# powersense.net
KiCad netlist of a schematic drawn in EAGLE
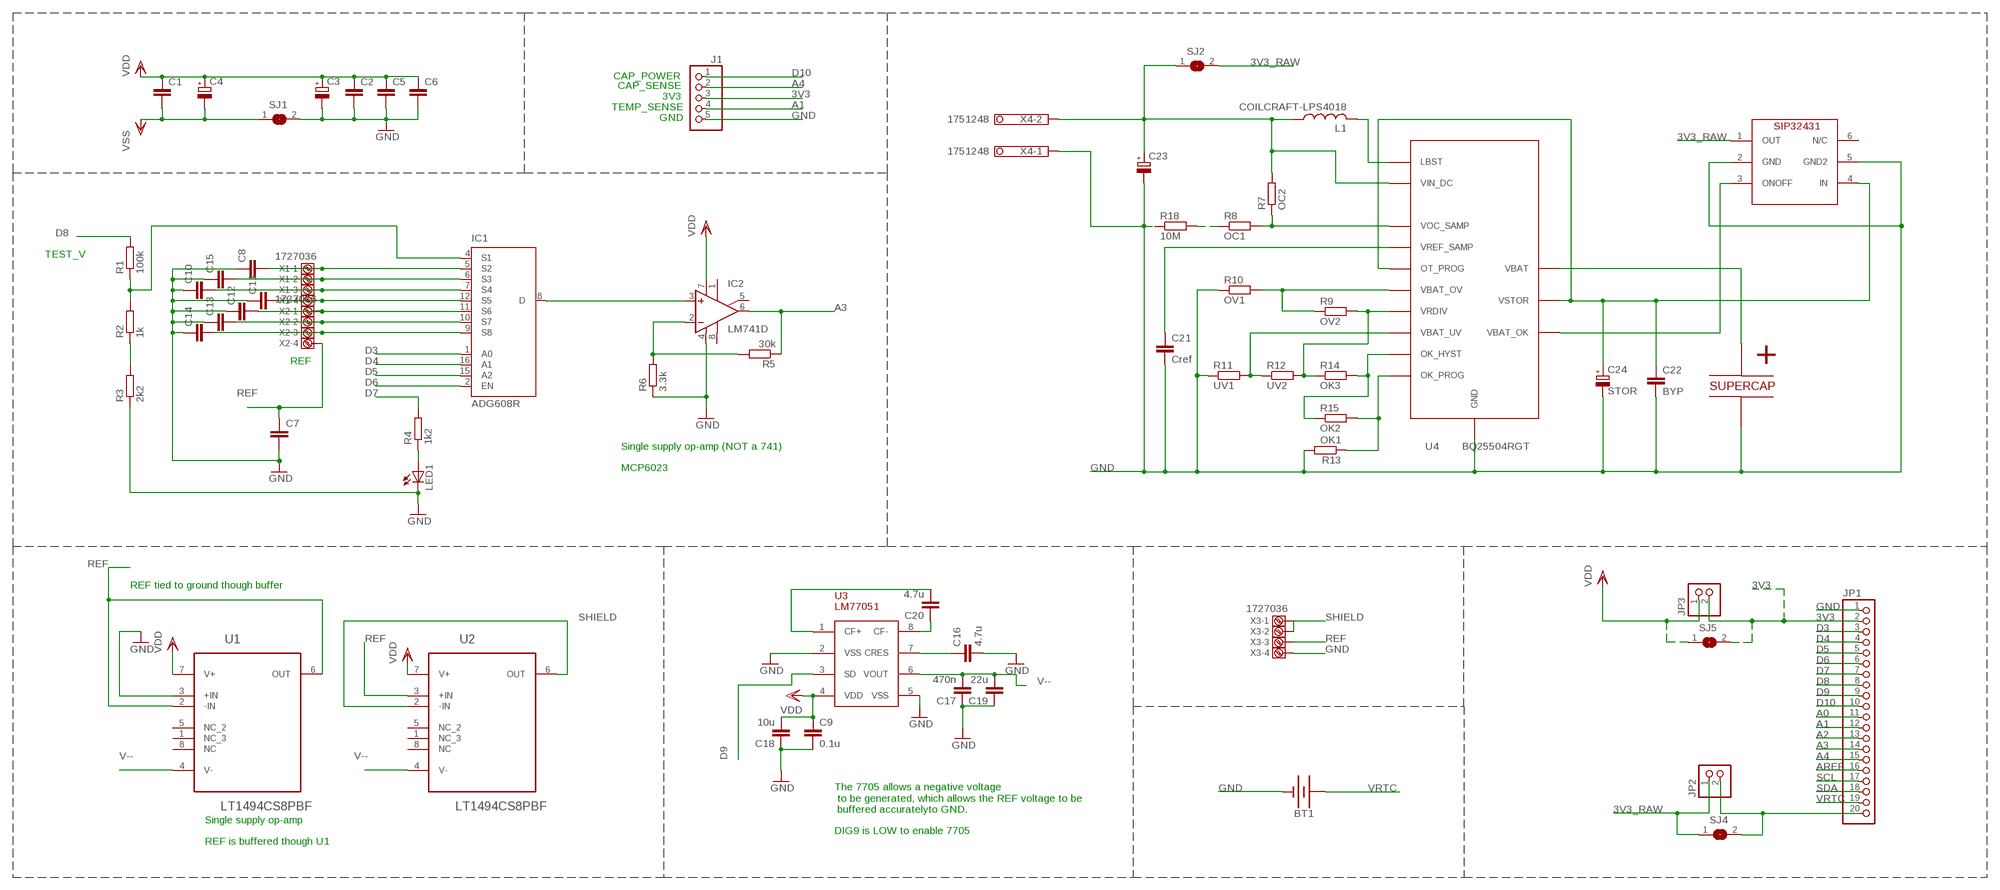
[diagram p0: schematic, sheet 1]

(export (version "E")
  (design (tool "Eeschema 10.0.6"))
  (components
    (comp (ref "BT1")
      (value "BATTERY-20MM_SMD")
      (footprint "eagle-import:BATTCON_20MM")
      (libsource (lib "eagle-import") (part "BATTERY-20MM_SMD"))
    )
    (comp (ref "C1")
      (value "C-EUC1206")
      (footprint "eagle-import:C1206")
      (libsource (lib "eagle-import") (part "C-EUC1206"))
    )
    (comp (ref "C2")
      (value "C-EUC1206")
      (footprint "eagle-import:C1206")
      (libsource (lib "eagle-import") (part "C-EUC1206"))
    )
    (comp (ref "C3")
      (value "CPOL-EUE5-6")
      (footprint "eagle-import:E5-6")
      (libsource (lib "eagle-import") (part "CPOL-EUE5-6"))
    )
    (comp (ref "C4")
      (value "CPOL-EUE5-6")
      (footprint "eagle-import:E5-6")
      (libsource (lib "eagle-import") (part "CPOL-EUE5-6"))
    )
    (comp (ref "C5")
      (value "C-EUC1206")
      (footprint "eagle-import:C1206")
      (libsource (lib "eagle-import") (part "C-EUC1206"))
    )
    (comp (ref "C6")
      (value "C-EUC1206")
      (footprint "eagle-import:C1206")
      (libsource (lib "eagle-import") (part "C-EUC1206"))
    )
    (comp (ref "C7")
      (value "C-EUC1206")
      (footprint "eagle-import:C1206")
      (libsource (lib "eagle-import") (part "C-EUC1206"))
    )
    (comp (ref "C8")
      (value "C-EUC1206")
      (footprint "eagle-import:C1206")
      (libsource (lib "eagle-import") (part "C-EUC1206"))
    )
    (comp (ref "C9")
      (value "0.1u")
      (footprint "eagle-import:C1206")
      (libsource (lib "eagle-import") (part "C-EUC1206"))
    )
    (comp (ref "C10")
      (value "C-EUC1206")
      (footprint "eagle-import:C1206")
      (libsource (lib "eagle-import") (part "C-EUC1206"))
    )
    (comp (ref "C11")
      (value "C-EUC1206")
      (footprint "eagle-import:C1206")
      (libsource (lib "eagle-import") (part "C-EUC1206"))
    )
    (comp (ref "C12")
      (value "C-EUC1206")
      (footprint "eagle-import:C1206")
      (libsource (lib "eagle-import") (part "C-EUC1206"))
    )
    (comp (ref "C13")
      (value "C-EUC1206")
      (footprint "eagle-import:C1206")
      (libsource (lib "eagle-import") (part "C-EUC1206"))
    )
    (comp (ref "C14")
      (value "C-EUC1206")
      (footprint "eagle-import:C1206")
      (libsource (lib "eagle-import") (part "C-EUC1206"))
    )
    (comp (ref "C15")
      (value "C-EUC1206")
      (footprint "eagle-import:C1206")
      (libsource (lib "eagle-import") (part "C-EUC1206"))
    )
    (comp (ref "C16")
      (value "4.7u")
      (footprint "eagle-import:C1206")
      (libsource (lib "eagle-import") (part "C-EUC1206"))
    )
    (comp (ref "C17")
      (value "470n")
      (footprint "eagle-import:C1206")
      (libsource (lib "eagle-import") (part "C-EUC1206"))
    )
    (comp (ref "C18")
      (value "10u")
      (footprint "eagle-import:C1206")
      (libsource (lib "eagle-import") (part "C-EUC1206"))
    )
    (comp (ref "C19")
      (value "22u")
      (footprint "eagle-import:C1206")
      (libsource (lib "eagle-import") (part "C-EUC1206"))
    )
    (comp (ref "C20")
      (value "4.7u")
      (footprint "eagle-import:C1206")
      (libsource (lib "eagle-import") (part "C-EUC1206"))
    )
    (comp (ref "C21")
      (value "Cref")
      (footprint "eagle-import:C1206")
      (libsource (lib "eagle-import") (part "C-EUC1206"))
    )
    (comp (ref "C22")
      (value "BYP")
      (footprint "eagle-import:C1206")
      (libsource (lib "eagle-import") (part "C-EUC1206"))
    )
    (comp (ref "C23")
      (value "CPOL-EUE5-6")
      (footprint "eagle-import:E5-6")
      (libsource (lib "eagle-import") (part "CPOL-EUE5-6"))
    )
    (comp (ref "C24")
      (value "STOR")
      (footprint "eagle-import:E5-6")
      (libsource (lib "eagle-import") (part "CPOL-EUE5-6"))
    )
    (comp (ref "IC1")
      (value "ADG608R")
      (footprint "eagle-import:SOIC16N")
      (libsource (lib "eagle-import") (part "ADG608R"))
    )
    (comp (ref "IC2")
      (value "LM741D")
      (footprint "eagle-import:SO08")
      (libsource (lib "eagle-import") (part "741DLM"))
    )
    (comp (ref "J1")
      (value "PINHD-1X5")
      (footprint "eagle-import:1X05")
      (libsource (lib "eagle-import") (part "PINHD-1X5"))
    )
    (comp (ref "JP1")
      (value "PINHD-1X20")
      (footprint "eagle-import:1X20")
      (libsource (lib "eagle-import") (part "PINHD-1X20"))
    )
    (comp (ref "JP2")
      (value "PINHD-1X2")
      (footprint "eagle-import:1X02")
      (libsource (lib "eagle-import") (part "PINHD-1X2"))
    )
    (comp (ref "JP3")
      (value "PINHD-1X2")
      (footprint "eagle-import:1X02")
      (libsource (lib "eagle-import") (part "PINHD-1X2"))
    )
    (comp (ref "L1")
      (value "COILCRAFT-LPS4018")
      (footprint "eagle-import:LPS4018")
      (libsource (lib "eagle-import") (part "COILCRAFT-LPS4018"))
    )
    (comp (ref "LED1")
      (value "LEDCHIPLED_0805")
      (footprint "eagle-import:CHIPLED_0805")
      (libsource (lib "eagle-import") (part "LEDCHIPLED_0805"))
    )
    (comp (ref "R1")
      (value "100k")
      (footprint "eagle-import:R1206")
      (libsource (lib "eagle-import") (part "R-EU_R1206"))
    )
    (comp (ref "R2")
      (value "1k")
      (footprint "eagle-import:R1206")
      (libsource (lib "eagle-import") (part "R-EU_R1206"))
    )
    (comp (ref "R3")
      (value "2k2")
      (footprint "eagle-import:R1206")
      (libsource (lib "eagle-import") (part "R-EU_R1206"))
    )
    (comp (ref "R4")
      (value "1k2")
      (footprint "eagle-import:R1206")
      (libsource (lib "eagle-import") (part "R-EU_R1206"))
    )
    (comp (ref "R5")
      (value "30k")
      (footprint "eagle-import:R1206")
      (libsource (lib "eagle-import") (part "R-EU_R1206"))
    )
    (comp (ref "R6")
      (value "3.3k")
      (footprint "eagle-import:R1206")
      (libsource (lib "eagle-import") (part "R-EU_R1206"))
    )
    (comp (ref "R7")
      (value "OC2")
      (footprint "eagle-import:R0603")
      (libsource (lib "eagle-import") (part "R-EU_R0603"))
    )
    (comp (ref "R8")
      (value "OC1")
      (footprint "eagle-import:R0603")
      (libsource (lib "eagle-import") (part "R-EU_R0603"))
    )
    (comp (ref "R9")
      (value "OV2")
      (footprint "eagle-import:R0603")
      (libsource (lib "eagle-import") (part "R-EU_R0603"))
    )
    (comp (ref "R10")
      (value "OV1")
      (footprint "eagle-import:R0603")
      (libsource (lib "eagle-import") (part "R-EU_R0603"))
    )
    (comp (ref "R11")
      (value "UV1")
      (footprint "eagle-import:R0603")
      (libsource (lib "eagle-import") (part "R-EU_R0603"))
    )
    (comp (ref "R12")
      (value "UV2")
      (footprint "eagle-import:R0603")
      (libsource (lib "eagle-import") (part "R-EU_R0603"))
    )
    (comp (ref "R13")
      (value "OK1")
      (footprint "eagle-import:R0603")
      (libsource (lib "eagle-import") (part "R-EU_R0603"))
    )
    (comp (ref "R14")
      (value "OK3")
      (footprint "eagle-import:R0603")
      (libsource (lib "eagle-import") (part "R-EU_R0603"))
    )
    (comp (ref "R15")
      (value "OK2")
      (footprint "eagle-import:R0603")
      (libsource (lib "eagle-import") (part "R-EU_R0603"))
    )
    (comp (ref "R18")
      (value "10M")
      (footprint "eagle-import:R0603")
      (libsource (lib "eagle-import") (part "R-EU_R0603"))
    )
    (comp (ref "SJ1") (value "SJ") (footprint "eagle-import:SJ") (libsource (lib "eagle-import") (part "SJ")))
    (comp (ref "SJ2") (value "SJ") (footprint "eagle-import:SJ") (libsource (lib "eagle-import") (part "SJ")))
    (comp (ref "SJ4") (value "SJ") (footprint "eagle-import:SJ") (libsource (lib "eagle-import") (part "SJ")))
    (comp (ref "SJ5") (value "SJ") (footprint "eagle-import:SJ") (libsource (lib "eagle-import") (part "SJ")))
    (comp (ref "U$2")
      (value "DDL105S05F1JRRDAPZ")
      (footprint "eagle-import:CAPF1J")
      (libsource (lib "eagle-import") (part "DDL105S05F1JRRDAPZ"))
    )
    (comp (ref "U1")
      (value "LT1494CS8PBF")
      (footprint "eagle-import:SOIC127P600X175-8N")
      (fields (field (name "MPN") "LT1494CS8#PBF"))
      (libsource (lib "eagle-import") (part "LT1494CS8PBF"))
    )
    (comp (ref "U2")
      (value "LT1494CS8PBF")
      (footprint "eagle-import:SOIC127P600X175-8N")
      (fields (field (name "MPN") "LT1494CS8#PBF"))
      (libsource (lib "eagle-import") (part "LT1494CS8PBF"))
    )
    (comp (ref "U3")
      (value "LM77051")
      (footprint "eagle-import:S-PDSO-G08_N")
      (libsource (lib "eagle-import") (part "LM77051"))
    )
    (comp (ref "U4")
      (value "BQ25504RGT")
      (footprint "eagle-import:S-PVQFN-N16")
      (libsource (lib "eagle-import") (part "BQ25504RGT"))
    )
    (comp (ref "U5")
      (value "SIP32431DR3")
      (footprint "eagle-import:SC-70-6")
      (libsource (lib "eagle-import") (part "SIP32431DR3"))
    )
    (comp (ref "X1")
      (value "1727036")
      (footprint "eagle-import:1727036")
      (fields (field (name "MF") "FARNELL"))
      (libsource (lib "eagle-import") (part "1727036"))
    )
    (comp (ref "X2")
      (value "1727036")
      (footprint "eagle-import:1727036")
      (fields (field (name "MF") "FARNELL"))
      (libsource (lib "eagle-import") (part "1727036"))
    )
    (comp (ref "X3")
      (value "1727036")
      (footprint "eagle-import:1727036")
      (fields (field (name "MF") "FARNELL"))
      (libsource (lib "eagle-import") (part "1727036"))
    )
    (comp (ref "X4")
      (value "1751248")
      (footprint "eagle-import:1751248")
      (libsource (lib "eagle-import") (part "1751248"))
    )
  )
  (nets
    (net (code "1") (name "/3V3") (class "Default")
      (node (ref "J1") (pin "3") (pinfunction "3_3") (pintype "passive"))
      (node (ref "JP1") (pin "2") (pinfunction "2_2") (pintype "passive"))
      (node (ref "JP3") (pin "2") (pinfunction "2_2") (pintype "passive"))
      (node (ref "SJ5") (pin "2") (pinfunction "2_2") (pintype "passive"))
    )
    (net (code "2") (name "/3V3_RAW") (class "Default")
      (node (ref "JP2") (pin "1") (pinfunction "1_1") (pintype "passive"))
      (node (ref "SJ2") (pin "2") (pinfunction "2_2") (pintype "passive"))
      (node (ref "SJ4") (pin "1") (pinfunction "1_1") (pintype "passive"))
      (node (ref "U5") (pin "1") (pinfunction "OUT_1") (pintype "bidirectional"))
    )
    (net (code "3") (name "/A0") (class "Default")
      (node (ref "JP1") (pin "11") (pinfunction "11_11") (pintype "passive"))
    )
    (net (code "4") (name "/A1") (class "Default")
      (node (ref "J1") (pin "4") (pinfunction "4_4") (pintype "passive"))
      (node (ref "JP1") (pin "12") (pinfunction "12_12") (pintype "passive"))
    )
    (net (code "5") (name "/A2") (class "Default")
      (node (ref "JP1") (pin "13") (pinfunction "13_13") (pintype "passive"))
    )
    (net (code "6") (name "/A3") (class "Default")
      (node (ref "IC2") (pin "6") (pinfunction "OUT_6") (pintype "output"))
      (node (ref "JP1") (pin "14") (pinfunction "14_14") (pintype "passive"))
      (node (ref "R5") (pin "1") (pinfunction "1_1") (pintype "passive"))
    )
    (net (code "7") (name "/A4") (class "Default")
      (node (ref "J1") (pin "2") (pinfunction "2_2") (pintype "passive"))
      (node (ref "JP1") (pin "15") (pinfunction "15_15") (pintype "passive"))
    )
    (net (code "8") (name "/AREF") (class "Default")
      (node (ref "JP1") (pin "16") (pinfunction "16_16") (pintype "passive"))
    )
    (net (code "9") (name "/D3") (class "Default")
      (node (ref "IC1") (pin "1") (pinfunction "A0_1") (pintype "input"))
      (node (ref "JP1") (pin "3") (pinfunction "3_3") (pintype "passive"))
    )
    (net (code "10") (name "/D4") (class "Default")
      (node (ref "IC1") (pin "16") (pinfunction "A1_16") (pintype "input"))
      (node (ref "JP1") (pin "4") (pinfunction "4_4") (pintype "passive"))
    )
    (net (code "11") (name "/D5") (class "Default")
      (node (ref "IC1") (pin "15") (pinfunction "A2_15") (pintype "input"))
      (node (ref "JP1") (pin "5") (pinfunction "5_5") (pintype "passive"))
    )
    (net (code "12") (name "/D6") (class "Default")
      (node (ref "IC1") (pin "2") (pinfunction "EN_2") (pintype "input"))
      (node (ref "JP1") (pin "6") (pinfunction "6_6") (pintype "passive"))
    )
    (net (code "13") (name "/D7") (class "Default")
      (node (ref "JP1") (pin "7") (pinfunction "7_7") (pintype "passive"))
      (node (ref "R4") (pin "2") (pinfunction "2_2") (pintype "passive"))
    )
    (net (code "14") (name "/D8") (class "Default")
      (node (ref "JP1") (pin "8") (pinfunction "8_8") (pintype "passive"))
      (node (ref "R1") (pin "2") (pinfunction "2_2") (pintype "passive"))
    )
    (net (code "15") (name "/D9") (class "Default")
      (node (ref "JP1") (pin "9") (pinfunction "9_9") (pintype "passive"))
      (node (ref "U3") (pin "3") (pinfunction "SD_3") (pintype "bidirectional"))
    )
    (net (code "16") (name "/D10") (class "Default")
      (node (ref "J1") (pin "1") (pinfunction "1_1") (pintype "passive"))
      (node (ref "JP1") (pin "10") (pinfunction "10_10") (pintype "passive"))
    )
    (net (code "17") (name "/REF") (class "Default")
      (node (ref "C7") (pin "1") (pinfunction "1_1") (pintype "passive"))
      (node (ref "U1") (pin "2") (pinfunction "-IN_2") (pintype "input"))
      (node (ref "U1") (pin "6") (pinfunction "OUT_6") (pintype "output"))
      (node (ref "U2") (pin "3") (pinfunction "+IN_3") (pintype "input"))
      (node (ref "X2") (pin "4") (pinfunction "1_4") (pintype "passive"))
      (node (ref "X3") (pin "3") (pinfunction "1_3") (pintype "passive"))
    )
    (net (code "18") (name "/SCL") (class "Default")
      (node (ref "JP1") (pin "17") (pinfunction "17_17") (pintype "passive"))
    )
    (net (code "19") (name "/SDA") (class "Default")
      (node (ref "JP1") (pin "18") (pinfunction "18_18") (pintype "passive"))
    )
    (net (code "20") (name "/SHIELD") (class "Default")
      (node (ref "U2") (pin "2") (pinfunction "-IN_2") (pintype "input"))
      (node (ref "U2") (pin "6") (pinfunction "OUT_6") (pintype "output"))
      (node (ref "X3") (pin "1") (pinfunction "1_1") (pintype "passive"))
      (node (ref "X3") (pin "2") (pinfunction "1_2") (pintype "passive"))
    )
    (net (code "21") (name "/V--") (class "Default")
      (node (ref "C17") (pin "2") (pinfunction "2_2") (pintype "passive"))
      (node (ref "C19") (pin "2") (pinfunction "2_2") (pintype "passive"))
      (node (ref "U1") (pin "4") (pinfunction "V-_4") (pintype "power_in"))
      (node (ref "U2") (pin "4") (pinfunction "V-_4") (pintype "power_in"))
      (node (ref "U3") (pin "6") (pinfunction "VOUT_6") (pintype "bidirectional"))
    )
    (net (code "22") (name "/VRTC") (class "Default")
      (node (ref "BT1") (pin "1") (pinfunction "+_1") (pintype "power_in"))
      (node (ref "JP1") (pin "19") (pinfunction "19_19") (pintype "passive"))
    )
    (net (code "23") (name "GND") (class "Default")
      (node (ref "BT1") (pin "2") (pinfunction "-_2") (pintype "power_in"))
      (node (ref "C10") (pin "1") (pinfunction "1_1") (pintype "passive"))
      (node (ref "C11") (pin "1") (pinfunction "1_1") (pintype "passive"))
      (node (ref "C12") (pin "1") (pinfunction "1_1") (pintype "passive"))
      (node (ref "C13") (pin "1") (pinfunction "1_1") (pintype "passive"))
      (node (ref "C14") (pin "1") (pinfunction "1_1") (pintype "passive"))
      (node (ref "C15") (pin "1") (pinfunction "1_1") (pintype "passive"))
      (node (ref "C16") (pin "2") (pinfunction "2_2") (pintype "passive"))
      (node (ref "C17") (pin "1") (pinfunction "1_1") (pintype "passive"))
      (node (ref "C18") (pin "1") (pinfunction "1_1") (pintype "passive"))
      (node (ref "C19") (pin "1") (pinfunction "1_1") (pintype "passive"))
      (node (ref "C2") (pin "2") (pinfunction "2_2") (pintype "passive"))
      (node (ref "C21") (pin "2") (pinfunction "2_2") (pintype "passive"))
      (node (ref "C22") (pin "2") (pinfunction "2_2") (pintype "passive"))
      (node (ref "C23") (pin "-") (pinfunction "-_-") (pintype "passive"))
      (node (ref "C24") (pin "-") (pinfunction "-_-") (pintype "passive"))
      (node (ref "C3") (pin "-") (pinfunction "-_-") (pintype "passive"))
      (node (ref "C5") (pin "2") (pinfunction "2_2") (pintype "passive"))
      (node (ref "C6") (pin "2") (pinfunction "2_2") (pintype "passive"))
      (node (ref "C7") (pin "2") (pinfunction "2_2") (pintype "passive"))
      (node (ref "C8") (pin "1") (pinfunction "1_1") (pintype "passive"))
      (node (ref "C9") (pin "2") (pinfunction "2_2") (pintype "passive"))
      (node (ref "IC2") (pin "4") (pinfunction "V-_4") (pintype "power_in"))
      (node (ref "J1") (pin "5") (pinfunction "5_5") (pintype "passive"))
      (node (ref "JP1") (pin "1") (pinfunction "1_1") (pintype "passive"))
      (node (ref "LED1") (pin "C") (pinfunction "C_C") (pintype "passive"))
      (node (ref "R10") (pin "1") (pinfunction "1_1") (pintype "passive"))
      (node (ref "R11") (pin "1") (pinfunction "1_1") (pintype "passive"))
      (node (ref "R13") (pin "2") (pinfunction "2_2") (pintype "passive"))
      (node (ref "R18") (pin "1") (pinfunction "1_1") (pintype "passive"))
      (node (ref "R3") (pin "1") (pinfunction "1_1") (pintype "passive"))
      (node (ref "R6") (pin "1") (pinfunction "1_1") (pintype "passive"))
      (node (ref "SJ1") (pin "2") (pinfunction "2_2") (pintype "passive"))
      (node (ref "U$2") (pin "P$2") (pinfunction "P$2_P$2") (pintype "bidirectional"))
      (node (ref "U1") (pin "3") (pinfunction "+IN_3") (pintype "input"))
      (node (ref "U3") (pin "2") (pinfunction "VSS_2") (pintype "bidirectional"))
      (node (ref "U3") (pin "5") (pinfunction "VSS_5") (pintype "bidirectional"))
      (node (ref "U4") (pin "1") (pinfunction "GND_1") (pintype "bidirectional"))
      (node (ref "U4") (pin "12") (pinfunction "GND_12") (pintype "bidirectional"))
      (node (ref "U4") (pin "13") (pinfunction "GND_13") (pintype "bidirectional"))
      (node (ref "U5") (pin "2") (pinfunction "GND_2") (pintype "bidirectional"))
      (node (ref "U5") (pin "5") (pinfunction "GND2_5") (pintype "bidirectional"))
      (node (ref "X3") (pin "4") (pinfunction "1_4") (pintype "passive"))
      (node (ref "X4") (pin "1") (pinfunction "K_1") (pintype "passive"))
    )
    (net (code "24") (name "Net-(IC1A-D)") (class "Default")
      (node (ref "IC1") (pin "8") (pinfunction "D_8") (pintype "bidirectional"))
      (node (ref "IC2") (pin "3") (pinfunction "+IN_3") (pintype "input"))
    )
    (net (code "25") (name "Net-(IC1A-S1)") (class "Default")
      (node (ref "IC1") (pin "4") (pinfunction "S1_4") (pintype "bidirectional"))
      (node (ref "R1") (pin "1") (pinfunction "1_1") (pintype "passive"))
      (node (ref "R2") (pin "2") (pinfunction "2_2") (pintype "passive"))
    )
    (net (code "26") (name "Net-(IC1A-S2)") (class "Default")
      (node (ref "C8") (pin "2") (pinfunction "2_2") (pintype "passive"))
      (node (ref "IC1") (pin "5") (pinfunction "S2_5") (pintype "bidirectional"))
      (node (ref "X1") (pin "1") (pinfunction "1_1") (pintype "passive"))
    )
    (net (code "27") (name "Net-(IC1A-S3)") (class "Default")
      (node (ref "C15") (pin "2") (pinfunction "2_2") (pintype "passive"))
      (node (ref "IC1") (pin "6") (pinfunction "S3_6") (pintype "bidirectional"))
      (node (ref "X1") (pin "2") (pinfunction "1_2") (pintype "passive"))
    )
    (net (code "28") (name "Net-(IC1A-S4)") (class "Default")
      (node (ref "C10") (pin "2") (pinfunction "2_2") (pintype "passive"))
      (node (ref "IC1") (pin "7") (pinfunction "S4_7") (pintype "bidirectional"))
      (node (ref "X1") (pin "3") (pinfunction "1_3") (pintype "passive"))
    )
    (net (code "29") (name "Net-(IC1A-S5)") (class "Default")
      (node (ref "C11") (pin "2") (pinfunction "2_2") (pintype "passive"))
      (node (ref "IC1") (pin "12") (pinfunction "S5_12") (pintype "bidirectional"))
      (node (ref "X1") (pin "4") (pinfunction "1_4") (pintype "passive"))
    )
    (net (code "30") (name "Net-(IC1A-S6)") (class "Default")
      (node (ref "C12") (pin "2") (pinfunction "2_2") (pintype "passive"))
      (node (ref "IC1") (pin "11") (pinfunction "S6_11") (pintype "bidirectional"))
      (node (ref "X2") (pin "1") (pinfunction "1_1") (pintype "passive"))
    )
    (net (code "31") (name "Net-(IC1A-S7)") (class "Default")
      (node (ref "C13") (pin "2") (pinfunction "2_2") (pintype "passive"))
      (node (ref "IC1") (pin "10") (pinfunction "S7_10") (pintype "bidirectional"))
      (node (ref "X2") (pin "2") (pinfunction "1_2") (pintype "passive"))
    )
    (net (code "32") (name "Net-(IC1A-S8)") (class "Default")
      (node (ref "C14") (pin "2") (pinfunction "2_2") (pintype "passive"))
      (node (ref "IC1") (pin "9") (pinfunction "S8_9") (pintype "bidirectional"))
      (node (ref "X2") (pin "3") (pinfunction "1_3") (pintype "passive"))
    )
    (net (code "33") (name "Net-(IC2--IN)") (class "Default")
      (node (ref "IC2") (pin "2") (pinfunction "-IN_2") (pintype "input"))
      (node (ref "R5") (pin "2") (pinfunction "2_2") (pintype "passive"))
      (node (ref "R6") (pin "2") (pinfunction "2_2") (pintype "passive"))
    )
    (net (code "34") (name "Net-(JP1-Pad20)") (class "Default")
      (node (ref "JP1") (pin "20") (pinfunction "20_20") (pintype "passive"))
      (node (ref "JP2") (pin "2") (pinfunction "2_2") (pintype "passive"))
      (node (ref "SJ4") (pin "2") (pinfunction "2_2") (pintype "passive"))
    )
    (net (code "35") (name "Net-(LED1-PadA)") (class "Default")
      (node (ref "LED1") (pin "A") (pinfunction "A_A") (pintype "passive"))
      (node (ref "R4") (pin "1") (pinfunction "1_1") (pintype "passive"))
    )
    (net (code "36") (name "Net-(R2-Pad1)") (class "Default")
      (node (ref "R2") (pin "1") (pinfunction "1_1") (pintype "passive"))
      (node (ref "R3") (pin "2") (pinfunction "2_2") (pintype "passive"))
    )
    (net (code "37") (name "Net-(R18-Pad2)") (class "Default")
      (node (ref "R18") (pin "2") (pinfunction "2_2") (pintype "passive"))
      (node (ref "R8") (pin "1") (pinfunction "1_1") (pintype "passive"))
    )
    (net (code "38") (name "Net-(U3-CF+)") (class "Default")
      (node (ref "C20") (pin "2") (pinfunction "2_2") (pintype "passive"))
      (node (ref "U3") (pin "1") (pinfunction "CF+_1") (pintype "bidirectional"))
    )
    (net (code "39") (name "Net-(U3-CF-)") (class "Default")
      (node (ref "C20") (pin "1") (pinfunction "1_1") (pintype "passive"))
      (node (ref "U3") (pin "8") (pinfunction "CF-_8") (pintype "bidirectional"))
    )
    (net (code "40") (name "Net-(U3-CRES)") (class "Default")
      (node (ref "C16") (pin "1") (pinfunction "1_1") (pintype "passive"))
      (node (ref "U3") (pin "7") (pinfunction "CRES_7") (pintype "bidirectional"))
    )
    (net (code "41") (name "Net-(U4-LBST)") (class "Default")
      (node (ref "L1") (pin "2") (pinfunction "2_2") (pintype "passive"))
      (node (ref "U4") (pin "16") (pinfunction "LBST_16") (pintype "bidirectional"))
    )
    (net (code "42") (name "Net-(U4-OK_HYST)") (class "Default")
      (node (ref "R14") (pin "2") (pinfunction "2_2") (pintype "passive"))
      (node (ref "R15") (pin "1") (pinfunction "1_1") (pintype "passive"))
      (node (ref "U4") (pin "9") (pinfunction "OK_HYST_9") (pintype "bidirectional"))
    )
    (net (code "43") (name "Net-(U4-OK_PROG)") (class "Default")
      (node (ref "R13") (pin "1") (pinfunction "1_1") (pintype "passive"))
      (node (ref "R15") (pin "2") (pinfunction "2_2") (pintype "passive"))
      (node (ref "U4") (pin "10") (pinfunction "OK_PROG_10") (pintype "bidirectional"))
    )
    (net (code "44") (name "Net-(U4-OT_PROG)") (class "Default")
      (node (ref "C22") (pin "1") (pinfunction "1_1") (pintype "passive"))
      (node (ref "C24") (pin "+") (pinfunction "+_+") (pintype "passive"))
      (node (ref "U4") (pin "15") (pinfunction "VSTOR_15") (pintype "bidirectional"))
      (node (ref "U4") (pin "5") (pinfunction "OT_PROG_5") (pintype "bidirectional"))
      (node (ref "U5") (pin "4") (pinfunction "IN_4") (pintype "bidirectional"))
    )
    (net (code "45") (name "Net-(U4-VBAT)") (class "Default")
      (node (ref "U$2") (pin "P$1") (pinfunction "P$1_P$1") (pintype "bidirectional"))
      (node (ref "U4") (pin "14") (pinfunction "VBAT_14") (pintype "bidirectional"))
    )
    (net (code "46") (name "Net-(U4-VBAT_OK)") (class "Default")
      (node (ref "U4") (pin "11") (pinfunction "VBAT_OK_11") (pintype "bidirectional"))
      (node (ref "U5") (pin "3") (pinfunction "ONOFF_3") (pintype "bidirectional"))
    )
    (net (code "47") (name "Net-(U4-VBAT_OV)") (class "Default")
      (node (ref "R10") (pin "2") (pinfunction "2_2") (pintype "passive"))
      (node (ref "R9") (pin "1") (pinfunction "1_1") (pintype "passive"))
      (node (ref "U4") (pin "6") (pinfunction "VBAT_OV_6") (pintype "bidirectional"))
    )
    (net (code "48") (name "Net-(U4-VBAT_UV)") (class "Default")
      (node (ref "R11") (pin "2") (pinfunction "2_2") (pintype "passive"))
      (node (ref "R12") (pin "1") (pinfunction "1_1") (pintype "passive"))
      (node (ref "U4") (pin "8") (pinfunction "VBAT_UV_8") (pintype "bidirectional"))
    )
    (net (code "49") (name "Net-(U4-VIN_DC)") (class "Default")
      (node (ref "C23") (pin "+") (pinfunction "+_+") (pintype "passive"))
      (node (ref "L1") (pin "1") (pinfunction "1_1") (pintype "passive"))
      (node (ref "R7") (pin "2") (pinfunction "2_2") (pintype "passive"))
      (node (ref "SJ2") (pin "1") (pinfunction "1_1") (pintype "passive"))
      (node (ref "U4") (pin "2") (pinfunction "VIN_DC_2") (pintype "bidirectional"))
      (node (ref "X4") (pin "2") (pinfunction "K_2") (pintype "passive"))
    )
    (net (code "50") (name "Net-(U4-VOC_SAMP)") (class "Default")
      (node (ref "R7") (pin "1") (pinfunction "1_1") (pintype "passive"))
      (node (ref "R8") (pin "2") (pinfunction "2_2") (pintype "passive"))
      (node (ref "U4") (pin "3") (pinfunction "VOC_SAMP_3") (pintype "bidirectional"))
    )
    (net (code "51") (name "Net-(U4-VRDIV)") (class "Default")
      (node (ref "R12") (pin "2") (pinfunction "2_2") (pintype "passive"))
      (node (ref "R14") (pin "1") (pinfunction "1_1") (pintype "passive"))
      (node (ref "R9") (pin "2") (pinfunction "2_2") (pintype "passive"))
      (node (ref "U4") (pin "7") (pinfunction "VRDIV_7") (pintype "bidirectional"))
    )
    (net (code "52") (name "Net-(U4-VREF_SAMP)") (class "Default")
      (node (ref "C21") (pin "1") (pinfunction "1_1") (pintype "passive"))
      (node (ref "U4") (pin "4") (pinfunction "VREF_SAMP_4") (pintype "bidirectional"))
    )
    (net (code "53") (name "VDD") (class "Default")
      (node (ref "C1") (pin "1") (pinfunction "1_1") (pintype "passive"))
      (node (ref "C18") (pin "2") (pinfunction "2_2") (pintype "passive"))
      (node (ref "C2") (pin "1") (pinfunction "1_1") (pintype "passive"))
      (node (ref "C3") (pin "+") (pinfunction "+_+") (pintype "passive"))
      (node (ref "C4") (pin "+") (pinfunction "+_+") (pintype "passive"))
      (node (ref "C5") (pin "1") (pinfunction "1_1") (pintype "passive"))
      (node (ref "C6") (pin "1") (pinfunction "1_1") (pintype "passive"))
      (node (ref "C9") (pin "1") (pinfunction "1_1") (pintype "passive"))
      (node (ref "IC2") (pin "7") (pinfunction "V+_7") (pintype "power_in"))
      (node (ref "JP3") (pin "1") (pinfunction "1_1") (pintype "passive"))
      (node (ref "SJ5") (pin "1") (pinfunction "1_1") (pintype "passive"))
      (node (ref "U1") (pin "7") (pinfunction "V+_7") (pintype "power_in"))
      (node (ref "U2") (pin "7") (pinfunction "V+_7") (pintype "power_in"))
      (node (ref "U3") (pin "4") (pinfunction "VDD_4") (pintype "bidirectional"))
    )
    (net (code "54") (name "VSS") (class "Default")
      (node (ref "C1") (pin "2") (pinfunction "2_2") (pintype "passive"))
      (node (ref "C4") (pin "-") (pinfunction "-_-") (pintype "passive"))
      (node (ref "SJ1") (pin "1") (pinfunction "1_1") (pintype "passive"))
    )
    (net (code "55") (name "unconnected-(IC2-ON1-Pad1)") (class "Default")
      (node (ref "IC2") (pin "1") (pinfunction "ON1_1") (pintype "passive"))
    )
    (net (code "56") (name "unconnected-(IC2-ON2-Pad5)") (class "Default")
      (node (ref "IC2") (pin "5") (pinfunction "ON2_5") (pintype "passive"))
    )
    (net (code "57") (name "unconnected-(IC2-OPT-Pad8)") (class "Default")
      (node (ref "IC2") (pin "8") (pinfunction "OPT_8") (pintype "passive"))
    )
    (net (code "58") (name "unconnected-(U1-NC-Pad8)") (class "Default")
      (node (ref "U1") (pin "8") (pinfunction "NC_8") (pintype "no_connect"))
    )
    (net (code "59") (name "unconnected-(U1-NC_2-Pad5)") (class "Default")
      (node (ref "U1") (pin "5") (pinfunction "NC_2_5") (pintype "no_connect"))
    )
    (net (code "60") (name "unconnected-(U1-NC_3-Pad1)") (class "Default")
      (node (ref "U1") (pin "1") (pinfunction "NC_3_1") (pintype "no_connect"))
    )
    (net (code "61") (name "unconnected-(U2-NC-Pad8)") (class "Default")
      (node (ref "U2") (pin "8") (pinfunction "NC_8") (pintype "no_connect"))
    )
    (net (code "62") (name "unconnected-(U2-NC_2-Pad5)") (class "Default")
      (node (ref "U2") (pin "5") (pinfunction "NC_2_5") (pintype "no_connect"))
    )
    (net (code "63") (name "unconnected-(U2-NC_3-Pad1)") (class "Default")
      (node (ref "U2") (pin "1") (pinfunction "NC_3_1") (pintype "no_connect"))
    )
    (net (code "64") (name "unconnected-(U5-N{slash}C-Pad6)") (class "Default")
      (node (ref "U5") (pin "6") (pinfunction "N/C_6") (pintype "bidirectional"))
    )
  )
)
